# DAC_GainOutputStage4.net
KiCad netlist of a schematic drawn in EAGLE
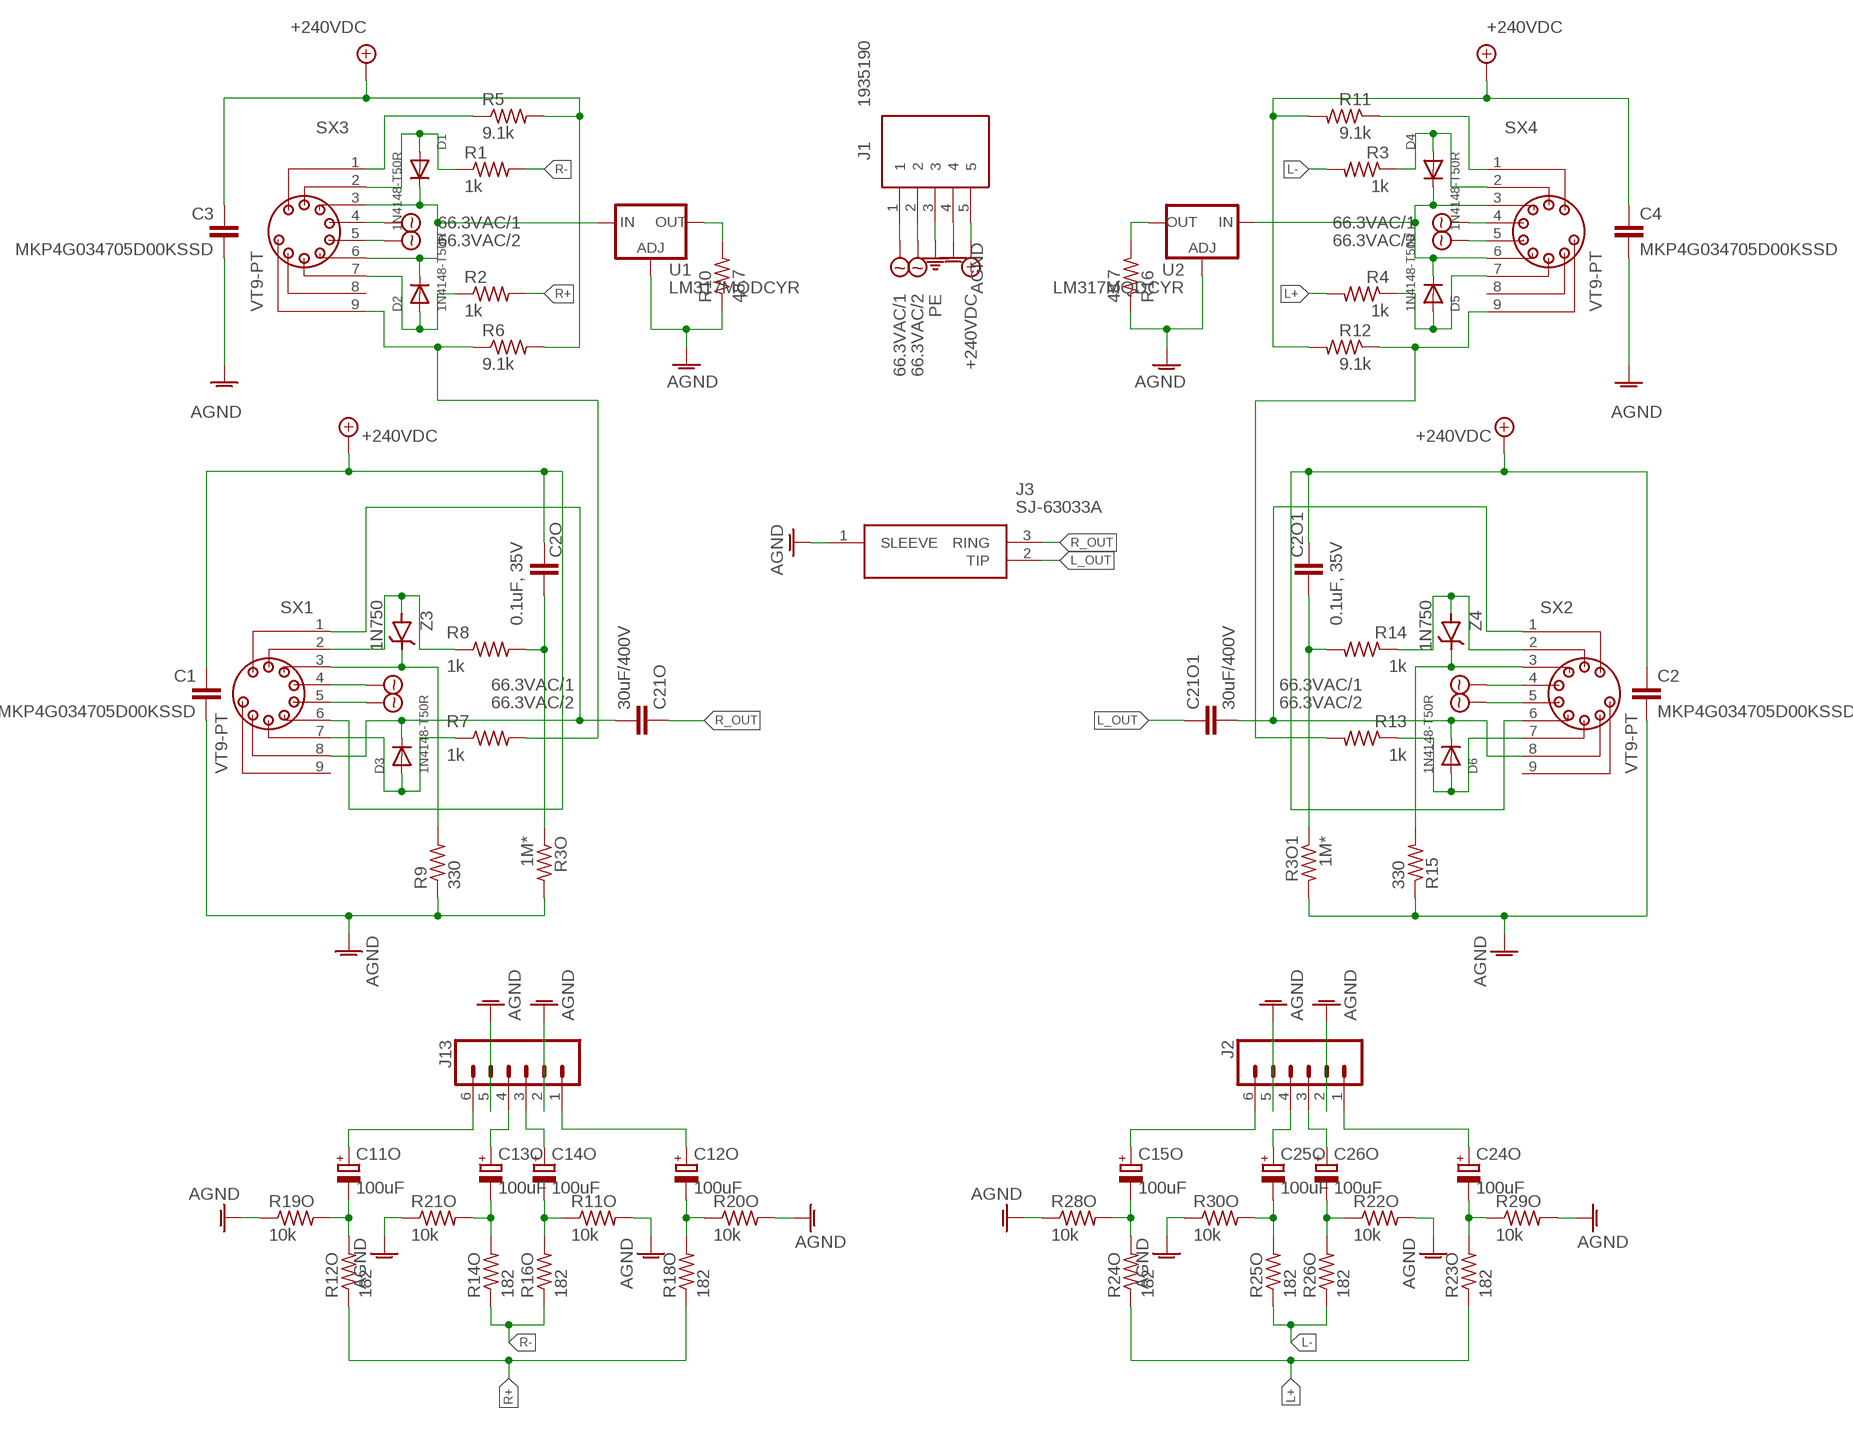
[diagram p0: schematic, sheet 1]

(export (version "E")
  (design (tool "Eeschema 10.0.6"))
  (components
    (comp (ref "C1")
      (value "MKP4G034705D00KSSD")
      (footprint "eagle-import:MKP4G034705D00KSSD")
      (fields (field (name "MOUSER_PART_NUMBER") "505-MKP4G034705DKSSD"))
      (libsource (lib "eagle-import") (part "MKP4G034705D00KSSD"))
    )
    (comp (ref "C2")
      (value "MKP4G034705D00KSSD")
      (footprint "eagle-import:MKP4G034705D00KSSD")
      (fields (field (name "MOUSER_PART_NUMBER") "505-MKP4G034705DKSSD"))
      (libsource (lib "eagle-import") (part "MKP4G034705D00KSSD"))
    )
    (comp (ref "C2O")
      (value "0.1uF, 35V")
      (footprint "eagle-import:MKS4B031002A00JC00")
      (fields
        (field (name "MANUFACTURER_PART_NUMBER") "MKS4B031002A00JC00")
        (field (name "MOUSER_PART_NUMBER") "505-MKS4B0312AJC")
      )
      (libsource (lib "eagle-import") (part "MKS4B031002A00JC00"))
    )
    (comp (ref "C2O1")
      (value "0.1uF, 35V")
      (footprint "eagle-import:MKS4B031002A00JC00")
      (fields
        (field (name "MANUFACTURER_PART_NUMBER") "MKS4B031002A00JC00")
        (field (name "MOUSER_PART_NUMBER") "505-MKS4B0312AJC")
      )
      (libsource (lib "eagle-import") (part "MKS4B031002A00JC00"))
    )
    (comp (ref "C3")
      (value "MKP4G034705D00KSSD")
      (footprint "eagle-import:MKP4G034705D00KSSD")
      (fields (field (name "MOUSER_PART_NUMBER") "505-MKP4G034705DKSSD"))
      (libsource (lib "eagle-import") (part "MKP4G034705D00KSSD"))
    )
    (comp (ref "C4")
      (value "MKP4G034705D00KSSD")
      (footprint "eagle-import:MKP4G034705D00KSSD")
      (fields (field (name "MOUSER_PART_NUMBER") "505-MKP4G034705DKSSD"))
      (libsource (lib "eagle-import") (part "MKP4G034705D00KSSD"))
    )
    (comp (ref "C11O")
      (value "100uF")
      (footprint "eagle-import:CAPPRD350W60D825H1300")
      (fields
        (field (name "ARROW_PART_NUMBER") "UFW1H101MPD1TD")
        (field (name "MOUSER_PART_NUMBER") "647-UFW1H101MPD1TD")
      )
      (libsource (lib "eagle-import") (part "UFW1H101MPD1TD"))
    )
    (comp (ref "C12O")
      (value "100uF")
      (footprint "eagle-import:CAPPRD350W60D825H1300")
      (fields
        (field (name "ARROW_PART_NUMBER") "UFW1H101MPD1TD")
        (field (name "MOUSER_PART_NUMBER") "647-UFW1H101MPD1TD")
      )
      (libsource (lib "eagle-import") (part "UFW1H101MPD1TD"))
    )
    (comp (ref "C13O")
      (value "100uF")
      (footprint "eagle-import:CAPPRD350W60D825H1300")
      (fields
        (field (name "ARROW_PART_NUMBER") "UFW1H101MPD1TD")
        (field (name "MOUSER_PART_NUMBER") "647-UFW1H101MPD1TD")
      )
      (libsource (lib "eagle-import") (part "UFW1H101MPD1TD"))
    )
    (comp (ref "C14O")
      (value "100uF")
      (footprint "eagle-import:CAPPRD350W60D825H1300")
      (fields
        (field (name "ARROW_PART_NUMBER") "UFW1H101MPD1TD")
        (field (name "MOUSER_PART_NUMBER") "647-UFW1H101MPD1TD")
      )
      (libsource (lib "eagle-import") (part "UFW1H101MPD1TD"))
    )
    (comp (ref "C15O")
      (value "100uF")
      (footprint "eagle-import:CAPPRD350W60D825H1300")
      (fields
        (field (name "ARROW_PART_NUMBER") "UFW1H101MPD1TD")
        (field (name "MOUSER_PART_NUMBER") "647-UFW1H101MPD1TD")
      )
      (libsource (lib "eagle-import") (part "UFW1H101MPD1TD"))
    )
    (comp (ref "C21O")
      (value "30uF/400V")
      (footprint "eagle-import:DCP4G053006ID2KSSD")
      (fields
        (field (name "MANUFACTURER_PART_NUMBER") "DCP4G053006ID2KSSD")
        (field (name "MOUSER_PART_NUMBER") "505-DCP4G0536ID2KSSD")
      )
      (libsource (lib "eagle-import") (part "DCP4G053006ID2KSSD"))
    )
    (comp (ref "C21O1")
      (value "30uF/400V")
      (footprint "eagle-import:DCP4G053006ID2KSSD")
      (fields
        (field (name "MANUFACTURER_PART_NUMBER") "DCP4G053006ID2KSSD")
        (field (name "MOUSER_PART_NUMBER") "505-DCP4G0536ID2KSSD")
      )
      (libsource (lib "eagle-import") (part "DCP4G053006ID2KSSD"))
    )
    (comp (ref "C24O")
      (value "100uF")
      (footprint "eagle-import:CAPPRD350W60D825H1300")
      (fields
        (field (name "ARROW_PART_NUMBER") "UFW1H101MPD1TD")
        (field (name "MOUSER_PART_NUMBER") "647-UFW1H101MPD1TD")
      )
      (libsource (lib "eagle-import") (part "UFW1H101MPD1TD"))
    )
    (comp (ref "C25O")
      (value "100uF")
      (footprint "eagle-import:CAPPRD350W60D825H1300")
      (fields
        (field (name "ARROW_PART_NUMBER") "UFW1H101MPD1TD")
        (field (name "MOUSER_PART_NUMBER") "647-UFW1H101MPD1TD")
      )
      (libsource (lib "eagle-import") (part "UFW1H101MPD1TD"))
    )
    (comp (ref "C26O")
      (value "100uF")
      (footprint "eagle-import:CAPPRD350W60D825H1300")
      (fields
        (field (name "ARROW_PART_NUMBER") "UFW1H101MPD1TD")
        (field (name "MOUSER_PART_NUMBER") "647-UFW1H101MPD1TD")
      )
      (libsource (lib "eagle-import") (part "UFW1H101MPD1TD"))
    )
    (comp (ref "D1")
      (value "1N4148-T50R")
      (footprint "eagle-import:DIOAD1068W53L380D172")
      (fields (field (name "MOUSER_PART_NUMBER") "512-1N4148T50R"))
      (libsource (lib "eagle-import") (part "1N4148-T50R"))
    )
    (comp (ref "D2")
      (value "1N4148-T50R")
      (footprint "eagle-import:DIOAD1068W53L380D172")
      (fields (field (name "MOUSER_PART_NUMBER") "512-1N4148T50R"))
      (libsource (lib "eagle-import") (part "1N4148-T50R"))
    )
    (comp (ref "D3")
      (value "1N4148-T50R")
      (footprint "eagle-import:DIOAD1068W53L380D172")
      (fields (field (name "MOUSER_PART_NUMBER") "512-1N4148T50R"))
      (libsource (lib "eagle-import") (part "1N4148-T50R"))
    )
    (comp (ref "D4")
      (value "1N4148-T50R")
      (footprint "eagle-import:DIOAD1068W53L380D172")
      (fields (field (name "MOUSER_PART_NUMBER") "512-1N4148T50R"))
      (libsource (lib "eagle-import") (part "1N4148-T50R"))
    )
    (comp (ref "D5")
      (value "1N4148-T50R")
      (footprint "eagle-import:DIOAD1068W53L380D172")
      (fields (field (name "MOUSER_PART_NUMBER") "512-1N4148T50R"))
      (libsource (lib "eagle-import") (part "1N4148-T50R"))
    )
    (comp (ref "D6")
      (value "1N4148-T50R")
      (footprint "eagle-import:DIOAD1068W53L380D172")
      (fields (field (name "MOUSER_PART_NUMBER") "512-1N4148T50R"))
      (libsource (lib "eagle-import") (part "1N4148-T50R"))
    )
    (comp (ref "J1")
      (value "1935190")
      (footprint "eagle-import:1935190")
      (fields (field (name "MOUSER_PART_NUMBER") "651-1935190"))
      (libsource (lib "eagle-import") (part "1935190"))
    )
    (comp (ref "J2")
      (value "CONN_06SILK_FEMALE_PTH")
      (footprint "eagle-import:1X06")
      (libsource (lib "eagle-import") (part "CONN_06SILK_FEMALE_PTH"))
    )
    (comp (ref "J3")
      (value "SJ-63033A")
      (footprint "eagle-import:SJ63033A")
      (libsource (lib "eagle-import") (part "SJ-63033A"))
    )
    (comp (ref "J13")
      (value "CONN_06SILK_FEMALE_PTH")
      (footprint "eagle-import:1X06")
      (libsource (lib "eagle-import") (part "CONN_06SILK_FEMALE_PTH"))
    )
    (comp (ref "R1")
      (value "1k")
      (footprint "eagle-import:0207_10")
      (fields
        (field (name "MANUFACTURER_PART_NUMBER") "LR1F1K0")
        (field (name "MOUSER_PART_NUMBER") "279-LR1F1K0")
      )
      (libsource (lib "eagle-import") (part "LR1F1K0"))
    )
    (comp (ref "R2")
      (value "1k")
      (footprint "eagle-import:0207_10")
      (fields
        (field (name "MANUFACTURER_PART_NUMBER") "LR1F1K0")
        (field (name "MOUSER_PART_NUMBER") "279-LR1F1K0")
      )
      (libsource (lib "eagle-import") (part "LR1F1K0"))
    )
    (comp (ref "R3")
      (value "1k")
      (footprint "eagle-import:0207_10")
      (fields
        (field (name "MANUFACTURER_PART_NUMBER") "LR1F1K0")
        (field (name "MOUSER_PART_NUMBER") "279-LR1F1K0")
      )
      (libsource (lib "eagle-import") (part "LR1F1K0"))
    )
    (comp (ref "R3O")
      (value "1M*")
      (footprint "eagle-import:0207_10")
      (fields
        (field (name "MANUFACTURER_PART_NUMBER") "LR1F1M0")
        (field (name "MOUSER_PART_NUMBER") "279-LR1F1M0")
      )
      (libsource (lib "eagle-import") (part "LR1F1M0"))
    )
    (comp (ref "R3O1")
      (value "1M*")
      (footprint "eagle-import:0207_10")
      (fields
        (field (name "MANUFACTURER_PART_NUMBER") "LR1F1M0")
        (field (name "MOUSER_PART_NUMBER") "279-LR1F1M0")
      )
      (libsource (lib "eagle-import") (part "LR1F1M0"))
    )
    (comp (ref "R4")
      (value "1k")
      (footprint "eagle-import:0207_10")
      (fields
        (field (name "MANUFACTURER_PART_NUMBER") "LR1F1K0")
        (field (name "MOUSER_PART_NUMBER") "279-LR1F1K0")
      )
      (libsource (lib "eagle-import") (part "LR1F1K0"))
    )
    (comp (ref "R5")
      (value "9.1k")
      (footprint "eagle-import:0411_15")
      (fields
        (field (name "MANUFACTURER_PART_NUMBER") "PR02000209101FA100")
        (field (name "MOUSER_PART_NUMBER") "594-PR02000209101FA1")
      )
      (libsource (lib "eagle-import") (part "PR02000209101FA100"))
    )
    (comp (ref "R6")
      (value "9.1k")
      (footprint "eagle-import:0411_15")
      (fields
        (field (name "MANUFACTURER_PART_NUMBER") "PR02000209101FA100")
        (field (name "MOUSER_PART_NUMBER") "594-PR02000209101FA1")
      )
      (libsource (lib "eagle-import") (part "PR02000209101FA100"))
    )
    (comp (ref "R7")
      (value "1k")
      (footprint "eagle-import:0207_10")
      (fields
        (field (name "MANUFACTURER_PART_NUMBER") "LR1F1K0")
        (field (name "MOUSER_PART_NUMBER") "279-LR1F1K0")
      )
      (libsource (lib "eagle-import") (part "LR1F1K0"))
    )
    (comp (ref "R8")
      (value "1k")
      (footprint "eagle-import:0207_10")
      (fields
        (field (name "MANUFACTURER_PART_NUMBER") "LR1F1K0")
        (field (name "MOUSER_PART_NUMBER") "279-LR1F1K0")
      )
      (libsource (lib "eagle-import") (part "LR1F1K0"))
    )
    (comp (ref "R9")
      (value "330")
      (footprint "eagle-import:0207_10")
      (fields
        (field (name "MANUFACTURER_PART_NUMBER") "LR1F330R")
        (field (name "MOUSER_PART_NUMBER") "279-LR1F330R")
      )
      (libsource (lib "eagle-import") (part "LR1F330R"))
    )
    (comp (ref "R10")
      (value "48.7")
      (footprint "eagle-import:0207_10")
      (libsource (lib "eagle-import") (part "R-US_0207/10"))
    )
    (comp (ref "R11")
      (value "9.1k")
      (footprint "eagle-import:0411_15")
      (fields
        (field (name "MANUFACTURER_PART_NUMBER") "PR02000209101FA100")
        (field (name "MOUSER_PART_NUMBER") "594-PR02000209101FA1")
      )
      (libsource (lib "eagle-import") (part "PR02000209101FA100"))
    )
    (comp (ref "R11O")
      (value "10k")
      (footprint "eagle-import:0207_10")
      (fields
        (field (name "MANUFACTURER_PART_NUMBER") "LR1F10K")
        (field (name "MOUSER_PART_NUMBER") "279-LR1F10K")
      )
      (libsource (lib "eagle-import") (part "LR1F10K"))
    )
    (comp (ref "R12")
      (value "9.1k")
      (footprint "eagle-import:0411_15")
      (fields
        (field (name "MANUFACTURER_PART_NUMBER") "PR02000209101FA100")
        (field (name "MOUSER_PART_NUMBER") "594-PR02000209101FA1")
      )
      (libsource (lib "eagle-import") (part "PR02000209101FA100"))
    )
    (comp (ref "R12O")
      (value "182")
      (footprint "eagle-import:0207_10")
      (fields
        (field (name "MANUFACTURER") "Yageo")
        (field (name "MANUFACTURER_PART_NUMBER") "MF0207FTE52-182R")
        (field (name "MOUSER_PART_NUMBER") "603-MF0207FTE52-182R")
      )
      (libsource (lib "eagle-import") (part "MF0207FTE52-182R"))
    )
    (comp (ref "R13")
      (value "1k")
      (footprint "eagle-import:0207_10")
      (fields
        (field (name "MANUFACTURER_PART_NUMBER") "LR1F1K0")
        (field (name "MOUSER_PART_NUMBER") "279-LR1F1K0")
      )
      (libsource (lib "eagle-import") (part "LR1F1K0"))
    )
    (comp (ref "R14")
      (value "1k")
      (footprint "eagle-import:0207_10")
      (fields
        (field (name "MANUFACTURER_PART_NUMBER") "LR1F1K0")
        (field (name "MOUSER_PART_NUMBER") "279-LR1F1K0")
      )
      (libsource (lib "eagle-import") (part "LR1F1K0"))
    )
    (comp (ref "R14O")
      (value "182")
      (footprint "eagle-import:0207_10")
      (fields
        (field (name "MANUFACTURER") "Yageo")
        (field (name "MANUFACTURER_PART_NUMBER") "MF0207FTE52-182R")
        (field (name "MOUSER_PART_NUMBER") "603-MF0207FTE52-182R")
      )
      (libsource (lib "eagle-import") (part "MF0207FTE52-182R"))
    )
    (comp (ref "R15")
      (value "330")
      (footprint "eagle-import:0207_10")
      (fields
        (field (name "MANUFACTURER_PART_NUMBER") "LR1F330R")
        (field (name "MOUSER_PART_NUMBER") "279-LR1F330R")
      )
      (libsource (lib "eagle-import") (part "LR1F330R"))
    )
    (comp (ref "R16")
      (value "48.7")
      (footprint "eagle-import:0207_10")
      (libsource (lib "eagle-import") (part "R-US_0207/10"))
    )
    (comp (ref "R16O")
      (value "182")
      (footprint "eagle-import:0207_10")
      (fields
        (field (name "MANUFACTURER") "Yageo")
        (field (name "MANUFACTURER_PART_NUMBER") "MF0207FTE52-182R")
        (field (name "MOUSER_PART_NUMBER") "603-MF0207FTE52-182R")
      )
      (libsource (lib "eagle-import") (part "MF0207FTE52-182R"))
    )
    (comp (ref "R18O")
      (value "182")
      (footprint "eagle-import:0207_10")
      (fields
        (field (name "MANUFACTURER") "Yageo")
        (field (name "MANUFACTURER_PART_NUMBER") "MF0207FTE52-182R")
        (field (name "MOUSER_PART_NUMBER") "603-MF0207FTE52-182R")
      )
      (libsource (lib "eagle-import") (part "MF0207FTE52-182R"))
    )
    (comp (ref "R19O")
      (value "10k")
      (footprint "eagle-import:0207_10")
      (fields
        (field (name "MANUFACTURER_PART_NUMBER") "LR1F10K")
        (field (name "MOUSER_PART_NUMBER") "279-LR1F10K")
      )
      (libsource (lib "eagle-import") (part "LR1F10K"))
    )
    (comp (ref "R20O")
      (value "10k")
      (footprint "eagle-import:0207_10")
      (fields
        (field (name "MANUFACTURER_PART_NUMBER") "LR1F10K")
        (field (name "MOUSER_PART_NUMBER") "279-LR1F10K")
      )
      (libsource (lib "eagle-import") (part "LR1F10K"))
    )
    (comp (ref "R21O")
      (value "10k")
      (footprint "eagle-import:0207_10")
      (fields
        (field (name "MANUFACTURER_PART_NUMBER") "LR1F10K")
        (field (name "MOUSER_PART_NUMBER") "279-LR1F10K")
      )
      (libsource (lib "eagle-import") (part "LR1F10K"))
    )
    (comp (ref "R22O")
      (value "10k")
      (footprint "eagle-import:0207_10")
      (fields
        (field (name "MANUFACTURER_PART_NUMBER") "LR1F10K")
        (field (name "MOUSER_PART_NUMBER") "279-LR1F10K")
      )
      (libsource (lib "eagle-import") (part "LR1F10K"))
    )
    (comp (ref "R23O")
      (value "182")
      (footprint "eagle-import:0207_10")
      (fields
        (field (name "MANUFACTURER") "Yageo")
        (field (name "MANUFACTURER_PART_NUMBER") "MF0207FTE52-182R")
        (field (name "MOUSER_PART_NUMBER") "603-MF0207FTE52-182R")
      )
      (libsource (lib "eagle-import") (part "MF0207FTE52-182R"))
    )
    (comp (ref "R24O")
      (value "182")
      (footprint "eagle-import:0207_10")
      (fields
        (field (name "MANUFACTURER") "Yageo")
        (field (name "MANUFACTURER_PART_NUMBER") "MF0207FTE52-182R")
        (field (name "MOUSER_PART_NUMBER") "603-MF0207FTE52-182R")
      )
      (libsource (lib "eagle-import") (part "MF0207FTE52-182R"))
    )
    (comp (ref "R25O")
      (value "182")
      (footprint "eagle-import:0207_10")
      (fields
        (field (name "MANUFACTURER") "Yageo")
        (field (name "MANUFACTURER_PART_NUMBER") "MF0207FTE52-182R")
        (field (name "MOUSER_PART_NUMBER") "603-MF0207FTE52-182R")
      )
      (libsource (lib "eagle-import") (part "MF0207FTE52-182R"))
    )
    (comp (ref "R26O")
      (value "182")
      (footprint "eagle-import:0207_10")
      (fields
        (field (name "MANUFACTURER") "Yageo")
        (field (name "MANUFACTURER_PART_NUMBER") "MF0207FTE52-182R")
        (field (name "MOUSER_PART_NUMBER") "603-MF0207FTE52-182R")
      )
      (libsource (lib "eagle-import") (part "MF0207FTE52-182R"))
    )
    (comp (ref "R28O")
      (value "10k")
      (footprint "eagle-import:0207_10")
      (fields
        (field (name "MANUFACTURER_PART_NUMBER") "LR1F10K")
        (field (name "MOUSER_PART_NUMBER") "279-LR1F10K")
      )
      (libsource (lib "eagle-import") (part "LR1F10K"))
    )
    (comp (ref "R29O")
      (value "10k")
      (footprint "eagle-import:0207_10")
      (fields
        (field (name "MANUFACTURER_PART_NUMBER") "LR1F10K")
        (field (name "MOUSER_PART_NUMBER") "279-LR1F10K")
      )
      (libsource (lib "eagle-import") (part "LR1F10K"))
    )
    (comp (ref "R30O")
      (value "10k")
      (footprint "eagle-import:0207_10")
      (fields
        (field (name "MANUFACTURER_PART_NUMBER") "LR1F10K")
        (field (name "MOUSER_PART_NUMBER") "279-LR1F10K")
      )
      (libsource (lib "eagle-import") (part "LR1F10K"))
    )
    (comp (ref "SX1")
      (value "VT9-PT")
      (footprint "eagle-import:VT9-PT")
      (libsource (lib "eagle-import") (part "VT9-PT"))
    )
    (comp (ref "SX2")
      (value "VT9-PT")
      (footprint "eagle-import:VT9-PT")
      (libsource (lib "eagle-import") (part "VT9-PT"))
    )
    (comp (ref "SX3")
      (value "VT9-PT")
      (footprint "eagle-import:VT9-PT")
      (libsource (lib "eagle-import") (part "VT9-PT"))
    )
    (comp (ref "SX4")
      (value "VT9-PT")
      (footprint "eagle-import:VT9-PT")
      (libsource (lib "eagle-import") (part "VT9-PT"))
    )
    (comp (ref "U1")
      (value "LM317MQDCYR")
      (footprint "eagle-import:SOT230P700X180-4N")
      (fields (field (name "MOUSER_PART_NUMBER") "595-LM317MQDCYR"))
      (libsource (lib "eagle-import") (part "LM317MQDCYR"))
    )
    (comp (ref "U2")
      (value "LM317MQDCYR")
      (footprint "eagle-import:SOT230P700X180-4N")
      (fields (field (name "MOUSER_PART_NUMBER") "595-LM317MQDCYR"))
      (libsource (lib "eagle-import") (part "LM317MQDCYR"))
    )
    (comp (ref "Z3")
      (value "1N750")
      (footprint "eagle-import:DIOAD1256W56L444D203")
      (fields (field (name "MOUSER_PART_NUMBER") "494-1N750(DO-35)"))
      (libsource (lib "eagle-import") (part "1N750"))
    )
    (comp (ref "Z4")
      (value "1N750")
      (footprint "eagle-import:DIOAD1256W56L444D203")
      (fields (field (name "MOUSER_PART_NUMBER") "494-1N750(DO-35)"))
      (libsource (lib "eagle-import") (part "1N750"))
    )
  )
  (nets
    (net (code "1") (name "+240VDC") (class "Default")
      (node (ref "C1") (pin "1") (pinfunction "1_1") (pintype "passive"))
      (node (ref "C2") (pin "1") (pinfunction "1_1") (pintype "passive"))
      (node (ref "C2O") (pin "1") (pinfunction "1_1") (pintype "passive"))
      (node (ref "C2O1") (pin "1") (pinfunction "1_1") (pintype "passive"))
      (node (ref "C3") (pin "1") (pinfunction "1_1") (pintype "passive"))
      (node (ref "C4") (pin "1") (pinfunction "1_1") (pintype "passive"))
      (node (ref "J1") (pin "5") (pinfunction "5_5") (pintype "bidirectional"))
      (node (ref "R11") (pin "2") (pinfunction "2_2") (pintype "passive"))
      (node (ref "R12") (pin "2") (pinfunction "2_2") (pintype "passive"))
      (node (ref "R5") (pin "2") (pinfunction "2_2") (pintype "passive"))
      (node (ref "R6") (pin "2") (pinfunction "2_2") (pintype "passive"))
      (node (ref "SX1") (pin "6") (pinfunction "6_6") (pintype "passive"))
      (node (ref "SX2") (pin "6") (pinfunction "6_6") (pintype "passive"))
    )
    (net (code "2") (name "66.3VAC{slash}1") (class "Default")
      (node (ref "J1") (pin "1") (pinfunction "1_1") (pintype "bidirectional"))
      (node (ref "SX1") (pin "4") (pinfunction "4_4") (pintype "passive"))
      (node (ref "SX2") (pin "4") (pinfunction "4_4") (pintype "passive"))
      (node (ref "SX3") (pin "4") (pinfunction "4_4") (pintype "passive"))
      (node (ref "SX4") (pin "4") (pinfunction "4_4") (pintype "passive"))
    )
    (net (code "3") (name "66.3VAC{slash}2") (class "Default")
      (node (ref "J1") (pin "2") (pinfunction "2_2") (pintype "bidirectional"))
      (node (ref "SX1") (pin "5") (pinfunction "5_5") (pintype "passive"))
      (node (ref "SX2") (pin "5") (pinfunction "5_5") (pintype "passive"))
      (node (ref "SX3") (pin "5") (pinfunction "5_5") (pintype "passive"))
      (node (ref "SX4") (pin "5") (pinfunction "5_5") (pintype "passive"))
    )
    (net (code "4") (name "AGND") (class "Default")
      (node (ref "C1") (pin "2") (pinfunction "2_2") (pintype "passive"))
      (node (ref "C2") (pin "2") (pinfunction "2_2") (pintype "passive"))
      (node (ref "C3") (pin "2") (pinfunction "2_2") (pintype "passive"))
      (node (ref "C4") (pin "2") (pinfunction "2_2") (pintype "passive"))
      (node (ref "J1") (pin "4") (pinfunction "4_4") (pintype "bidirectional"))
      (node (ref "J13") (pin "2") (pinfunction "2_2") (pintype "passive"))
      (node (ref "J13") (pin "5") (pinfunction "5_5") (pintype "passive"))
      (node (ref "J2") (pin "2") (pinfunction "2_2") (pintype "passive"))
      (node (ref "J2") (pin "5") (pinfunction "5_5") (pintype "passive"))
      (node (ref "J3") (pin "1") (pinfunction "SLEEVE_1") (pintype "bidirectional"))
      (node (ref "R10") (pin "1") (pinfunction "1_1") (pintype "passive"))
      (node (ref "R11O") (pin "2") (pinfunction "2_2") (pintype "passive"))
      (node (ref "R15") (pin "1") (pinfunction "1_1") (pintype "passive"))
      (node (ref "R16") (pin "1") (pinfunction "1_1") (pintype "passive"))
      (node (ref "R19O") (pin "1") (pinfunction "1_1") (pintype "passive"))
      (node (ref "R20O") (pin "2") (pinfunction "2_2") (pintype "passive"))
      (node (ref "R21O") (pin "1") (pinfunction "1_1") (pintype "passive"))
      (node (ref "R22O") (pin "2") (pinfunction "2_2") (pintype "passive"))
      (node (ref "R28O") (pin "1") (pinfunction "1_1") (pintype "passive"))
      (node (ref "R29O") (pin "2") (pinfunction "2_2") (pintype "passive"))
      (node (ref "R30O") (pin "1") (pinfunction "1_1") (pintype "passive"))
      (node (ref "R3O") (pin "2") (pinfunction "2_2") (pintype "passive"))
      (node (ref "R3O1") (pin "2") (pinfunction "2_2") (pintype "passive"))
      (node (ref "R9") (pin "1") (pinfunction "1_1") (pintype "passive"))
      (node (ref "U1") (pin "1") (pinfunction "ADJ_1") (pintype "input"))
      (node (ref "U2") (pin "1") (pinfunction "ADJ_1") (pintype "input"))
    )
    (net (code "5") (name "L+") (class "Default")
      (node (ref "R23O") (pin "1") (pinfunction "1_1") (pintype "passive"))
      (node (ref "R24O") (pin "1") (pinfunction "1_1") (pintype "passive"))
      (node (ref "R4") (pin "2") (pinfunction "2_2") (pintype "passive"))
    )
    (net (code "6") (name "L-") (class "Default")
      (node (ref "R25O") (pin "1") (pinfunction "1_1") (pintype "passive"))
      (node (ref "R26O") (pin "1") (pinfunction "1_1") (pintype "passive"))
      (node (ref "R3") (pin "2") (pinfunction "2_2") (pintype "passive"))
    )
    (net (code "7") (name "L_OUT") (class "Default")
      (node (ref "C21O1") (pin "1") (pinfunction "1_1") (pintype "passive"))
      (node (ref "J3") (pin "2") (pinfunction "TIP_2") (pintype "bidirectional"))
    )
    (net (code "8") (name "Net-(C2O-Pad2)") (class "Default")
      (node (ref "C2O") (pin "2") (pinfunction "2_2") (pintype "passive"))
      (node (ref "R3O") (pin "1") (pinfunction "1_1") (pintype "passive"))
      (node (ref "R8") (pin "2") (pinfunction "2_2") (pintype "passive"))
    )
    (net (code "9") (name "Net-(C2O1-Pad2)") (class "Default")
      (node (ref "C2O1") (pin "2") (pinfunction "2_2") (pintype "passive"))
      (node (ref "R14") (pin "2") (pinfunction "2_2") (pintype "passive"))
      (node (ref "R3O1") (pin "1") (pinfunction "1_1") (pintype "passive"))
    )
    (net (code "10") (name "Net-(C11O-+)") (class "Default")
      (node (ref "C11O") (pin "1") (pinfunction "+_1") (pintype "passive"))
      (node (ref "J13") (pin "6") (pinfunction "6_6") (pintype "passive"))
    )
    (net (code "11") (name "Net-(C11O--)") (class "Default")
      (node (ref "C11O") (pin "2") (pinfunction "-_2") (pintype "passive"))
      (node (ref "R12O") (pin "2") (pinfunction "2_2") (pintype "passive"))
      (node (ref "R19O") (pin "2") (pinfunction "2_2") (pintype "passive"))
    )
    (net (code "12") (name "Net-(C12O-+)") (class "Default")
      (node (ref "C12O") (pin "1") (pinfunction "+_1") (pintype "passive"))
      (node (ref "J13") (pin "1") (pinfunction "1_1") (pintype "passive"))
    )
    (net (code "13") (name "Net-(C12O--)") (class "Default")
      (node (ref "C12O") (pin "2") (pinfunction "-_2") (pintype "passive"))
      (node (ref "R18O") (pin "2") (pinfunction "2_2") (pintype "passive"))
      (node (ref "R20O") (pin "1") (pinfunction "1_1") (pintype "passive"))
    )
    (net (code "14") (name "Net-(C13O-+)") (class "Default")
      (node (ref "C13O") (pin "1") (pinfunction "+_1") (pintype "passive"))
      (node (ref "J13") (pin "4") (pinfunction "4_4") (pintype "passive"))
    )
    (net (code "15") (name "Net-(C13O--)") (class "Default")
      (node (ref "C13O") (pin "2") (pinfunction "-_2") (pintype "passive"))
      (node (ref "R14O") (pin "2") (pinfunction "2_2") (pintype "passive"))
      (node (ref "R21O") (pin "2") (pinfunction "2_2") (pintype "passive"))
    )
    (net (code "16") (name "Net-(C14O-+)") (class "Default")
      (node (ref "C14O") (pin "1") (pinfunction "+_1") (pintype "passive"))
      (node (ref "J13") (pin "3") (pinfunction "3_3") (pintype "passive"))
    )
    (net (code "17") (name "Net-(C14O--)") (class "Default")
      (node (ref "C14O") (pin "2") (pinfunction "-_2") (pintype "passive"))
      (node (ref "R11O") (pin "1") (pinfunction "1_1") (pintype "passive"))
      (node (ref "R16O") (pin "2") (pinfunction "2_2") (pintype "passive"))
    )
    (net (code "18") (name "Net-(C15O-+)") (class "Default")
      (node (ref "C15O") (pin "1") (pinfunction "+_1") (pintype "passive"))
      (node (ref "J2") (pin "6") (pinfunction "6_6") (pintype "passive"))
    )
    (net (code "19") (name "Net-(C15O--)") (class "Default")
      (node (ref "C15O") (pin "2") (pinfunction "-_2") (pintype "passive"))
      (node (ref "R24O") (pin "2") (pinfunction "2_2") (pintype "passive"))
      (node (ref "R28O") (pin "2") (pinfunction "2_2") (pintype "passive"))
    )
    (net (code "20") (name "Net-(C24O-+)") (class "Default")
      (node (ref "C24O") (pin "1") (pinfunction "+_1") (pintype "passive"))
      (node (ref "J2") (pin "1") (pinfunction "1_1") (pintype "passive"))
    )
    (net (code "21") (name "Net-(C24O--)") (class "Default")
      (node (ref "C24O") (pin "2") (pinfunction "-_2") (pintype "passive"))
      (node (ref "R23O") (pin "2") (pinfunction "2_2") (pintype "passive"))
      (node (ref "R29O") (pin "1") (pinfunction "1_1") (pintype "passive"))
    )
    (net (code "22") (name "Net-(C25O-+)") (class "Default")
      (node (ref "C25O") (pin "1") (pinfunction "+_1") (pintype "passive"))
      (node (ref "J2") (pin "4") (pinfunction "4_4") (pintype "passive"))
    )
    (net (code "23") (name "Net-(C25O--)") (class "Default")
      (node (ref "C25O") (pin "2") (pinfunction "-_2") (pintype "passive"))
      (node (ref "R25O") (pin "2") (pinfunction "2_2") (pintype "passive"))
      (node (ref "R30O") (pin "2") (pinfunction "2_2") (pintype "passive"))
    )
    (net (code "24") (name "Net-(C26O-+)") (class "Default")
      (node (ref "C26O") (pin "1") (pinfunction "+_1") (pintype "passive"))
      (node (ref "J2") (pin "3") (pinfunction "3_3") (pintype "passive"))
    )
    (net (code "25") (name "Net-(C26O--)") (class "Default")
      (node (ref "C26O") (pin "2") (pinfunction "-_2") (pintype "passive"))
      (node (ref "R22O") (pin "1") (pinfunction "1_1") (pintype "passive"))
      (node (ref "R26O") (pin "2") (pinfunction "2_2") (pintype "passive"))
    )
    (net (code "26") (name "Net-(D1-A)") (class "Default")
      (node (ref "D1") (pin "2") (pinfunction "A_2") (pintype "passive"))
      (node (ref "R1") (pin "1") (pinfunction "1_1") (pintype "passive"))
      (node (ref "SX3") (pin "2") (pinfunction "2_2") (pintype "passive"))
    )
    (net (code "27") (name "Net-(D1-C)") (class "Default")
      (node (ref "D1") (pin "1") (pinfunction "C_1") (pintype "passive"))
      (node (ref "D2") (pin "1") (pinfunction "C_1") (pintype "passive"))
      (node (ref "SX3") (pin "3") (pinfunction "3_3") (pintype "passive"))
      (node (ref "SX3") (pin "6") (pinfunction "6_6") (pintype "passive"))
      (node (ref "U1") (pin "3") (pinfunction "IN_3") (pintype "input"))
    )
    (net (code "28") (name "Net-(D2-A)") (class "Default")
      (node (ref "D2") (pin "2") (pinfunction "A_2") (pintype "passive"))
      (node (ref "R2") (pin "1") (pinfunction "1_1") (pintype "passive"))
      (node (ref "SX3") (pin "7") (pinfunction "7_7") (pintype "passive"))
    )
    (net (code "29") (name "Net-(D3-A)") (class "Default")
      (node (ref "D3") (pin "2") (pinfunction "A_2") (pintype "passive"))
      (node (ref "R7") (pin "1") (pinfunction "1_1") (pintype "passive"))
      (node (ref "SX1") (pin "7") (pinfunction "7_7") (pintype "passive"))
    )
    (net (code "30") (name "Net-(D3-C)") (class "Default")
      (node (ref "C21O") (pin "2") (pinfunction "2_2") (pintype "passive"))
      (node (ref "D3") (pin "1") (pinfunction "C_1") (pintype "passive"))
      (node (ref "SX1") (pin "1") (pinfunction "1_1") (pintype "passive"))
      (node (ref "SX1") (pin "8") (pinfunction "8_8") (pintype "passive"))
    )
    (net (code "31") (name "Net-(D4-A)") (class "Default")
      (node (ref "D4") (pin "2") (pinfunction "A_2") (pintype "passive"))
      (node (ref "R3") (pin "1") (pinfunction "1_1") (pintype "passive"))
      (node (ref "SX4") (pin "2") (pinfunction "2_2") (pintype "passive"))
    )
    (net (code "32") (name "Net-(D4-C)") (class "Default")
      (node (ref "D4") (pin "1") (pinfunction "C_1") (pintype "passive"))
      (node (ref "D5") (pin "1") (pinfunction "C_1") (pintype "passive"))
      (node (ref "SX4") (pin "3") (pinfunction "3_3") (pintype "passive"))
      (node (ref "SX4") (pin "6") (pinfunction "6_6") (pintype "passive"))
      (node (ref "U2") (pin "3") (pinfunction "IN_3") (pintype "input"))
    )
    (net (code "33") (name "Net-(D5-A)") (class "Default")
      (node (ref "D5") (pin "2") (pinfunction "A_2") (pintype "passive"))
      (node (ref "R4") (pin "1") (pinfunction "1_1") (pintype "passive"))
      (node (ref "SX4") (pin "7") (pinfunction "7_7") (pintype "passive"))
    )
    (net (code "34") (name "Net-(D6-A)") (class "Default")
      (node (ref "D6") (pin "2") (pinfunction "A_2") (pintype "passive"))
      (node (ref "R13") (pin "1") (pinfunction "1_1") (pintype "passive"))
      (node (ref "SX2") (pin "7") (pinfunction "7_7") (pintype "passive"))
    )
    (net (code "35") (name "Net-(D6-C)") (class "Default")
      (node (ref "C21O1") (pin "2") (pinfunction "2_2") (pintype "passive"))
      (node (ref "D6") (pin "1") (pinfunction "C_1") (pintype "passive"))
      (node (ref "SX2") (pin "1") (pinfunction "1_1") (pintype "passive"))
      (node (ref "SX2") (pin "8") (pinfunction "8_8") (pintype "passive"))
    )
    (net (code "36") (name "Net-(R5-Pad1)") (class "Default")
      (node (ref "R5") (pin "1") (pinfunction "1_1") (pintype "passive"))
      (node (ref "SX3") (pin "1") (pinfunction "1_1") (pintype "passive"))
    )
    (net (code "37") (name "Net-(R6-Pad1)") (class "Default")
      (node (ref "R6") (pin "1") (pinfunction "1_1") (pintype "passive"))
      (node (ref "R7") (pin "2") (pinfunction "2_2") (pintype "passive"))
      (node (ref "SX3") (pin "9") (pinfunction "9_9") (pintype "passive"))
    )
    (net (code "38") (name "Net-(R10-Pad2)") (class "Default")
      (node (ref "R10") (pin "2") (pinfunction "2_2") (pintype "passive"))
      (node (ref "U1") (pin "2") (pinfunction "OUT_2") (pintype "passive"))
      (node (ref "U1") (pin "4") (pinfunction "OUT_4") (pintype "passive"))
    )
    (net (code "39") (name "Net-(R11-Pad1)") (class "Default")
      (node (ref "R11") (pin "1") (pinfunction "1_1") (pintype "passive"))
      (node (ref "SX4") (pin "1") (pinfunction "1_1") (pintype "passive"))
    )
    (net (code "40") (name "Net-(R12-Pad1)") (class "Default")
      (node (ref "R12") (pin "1") (pinfunction "1_1") (pintype "passive"))
      (node (ref "R13") (pin "2") (pinfunction "2_2") (pintype "passive"))
      (node (ref "SX4") (pin "9") (pinfunction "9_9") (pintype "passive"))
    )
    (net (code "41") (name "Net-(R16-Pad2)") (class "Default")
      (node (ref "R16") (pin "2") (pinfunction "2_2") (pintype "passive"))
      (node (ref "U2") (pin "2") (pinfunction "OUT_2") (pintype "passive"))
      (node (ref "U2") (pin "4") (pinfunction "OUT_4") (pintype "passive"))
    )
    (net (code "42") (name "Net-(Z3-A)") (class "Default")
      (node (ref "R8") (pin "1") (pinfunction "1_1") (pintype "passive"))
      (node (ref "SX1") (pin "2") (pinfunction "2_2") (pintype "passive"))
      (node (ref "Z3") (pin "2") (pinfunction "A_2") (pintype "passive"))
    )
    (net (code "43") (name "Net-(Z3-C)") (class "Default")
      (node (ref "R9") (pin "2") (pinfunction "2_2") (pintype "passive"))
      (node (ref "SX1") (pin "3") (pinfunction "3_3") (pintype "passive"))
      (node (ref "Z3") (pin "1") (pinfunction "C_1") (pintype "passive"))
    )
    (net (code "44") (name "Net-(Z4-A)") (class "Default")
      (node (ref "R14") (pin "1") (pinfunction "1_1") (pintype "passive"))
      (node (ref "SX2") (pin "2") (pinfunction "2_2") (pintype "passive"))
      (node (ref "Z4") (pin "2") (pinfunction "A_2") (pintype "passive"))
    )
    (net (code "45") (name "Net-(Z4-C)") (class "Default")
      (node (ref "R15") (pin "2") (pinfunction "2_2") (pintype "passive"))
      (node (ref "SX2") (pin "3") (pinfunction "3_3") (pintype "passive"))
      (node (ref "Z4") (pin "1") (pinfunction "C_1") (pintype "passive"))
    )
    (net (code "46") (name "PE") (class "Default")
      (node (ref "J1") (pin "3") (pinfunction "3_3") (pintype "bidirectional"))
    )
    (net (code "47") (name "R+") (class "Default")
      (node (ref "R12O") (pin "1") (pinfunction "1_1") (pintype "passive"))
      (node (ref "R18O") (pin "1") (pinfunction "1_1") (pintype "passive"))
      (node (ref "R2") (pin "2") (pinfunction "2_2") (pintype "passive"))
    )
    (net (code "48") (name "R-") (class "Default")
      (node (ref "R1") (pin "2") (pinfunction "2_2") (pintype "passive"))
      (node (ref "R14O") (pin "1") (pinfunction "1_1") (pintype "passive"))
      (node (ref "R16O") (pin "1") (pinfunction "1_1") (pintype "passive"))
    )
    (net (code "49") (name "R_OUT") (class "Default")
      (node (ref "C21O") (pin "1") (pinfunction "1_1") (pintype "passive"))
      (node (ref "J3") (pin "3") (pinfunction "RING_3") (pintype "bidirectional"))
    )
    (net (code "50") (name "unconnected-(SX1-Pad9)") (class "Default")
      (node (ref "SX1") (pin "9") (pinfunction "9_9") (pintype "passive"))
    )
    (net (code "51") (name "unconnected-(SX2-Pad9)") (class "Default")
      (node (ref "SX2") (pin "9") (pinfunction "9_9") (pintype "passive"))
    )
    (net (code "52") (name "unconnected-(SX3-Pad8)") (class "Default")
      (node (ref "SX3") (pin "8") (pinfunction "8_8") (pintype "passive"))
    )
    (net (code "53") (name "unconnected-(SX4-Pad8)") (class "Default")
      (node (ref "SX4") (pin "8") (pinfunction "8_8") (pintype "passive"))
    )
  )
)
